# Stepper_driver_1_0.net
KiCad netlist of a schematic drawn in EAGLE
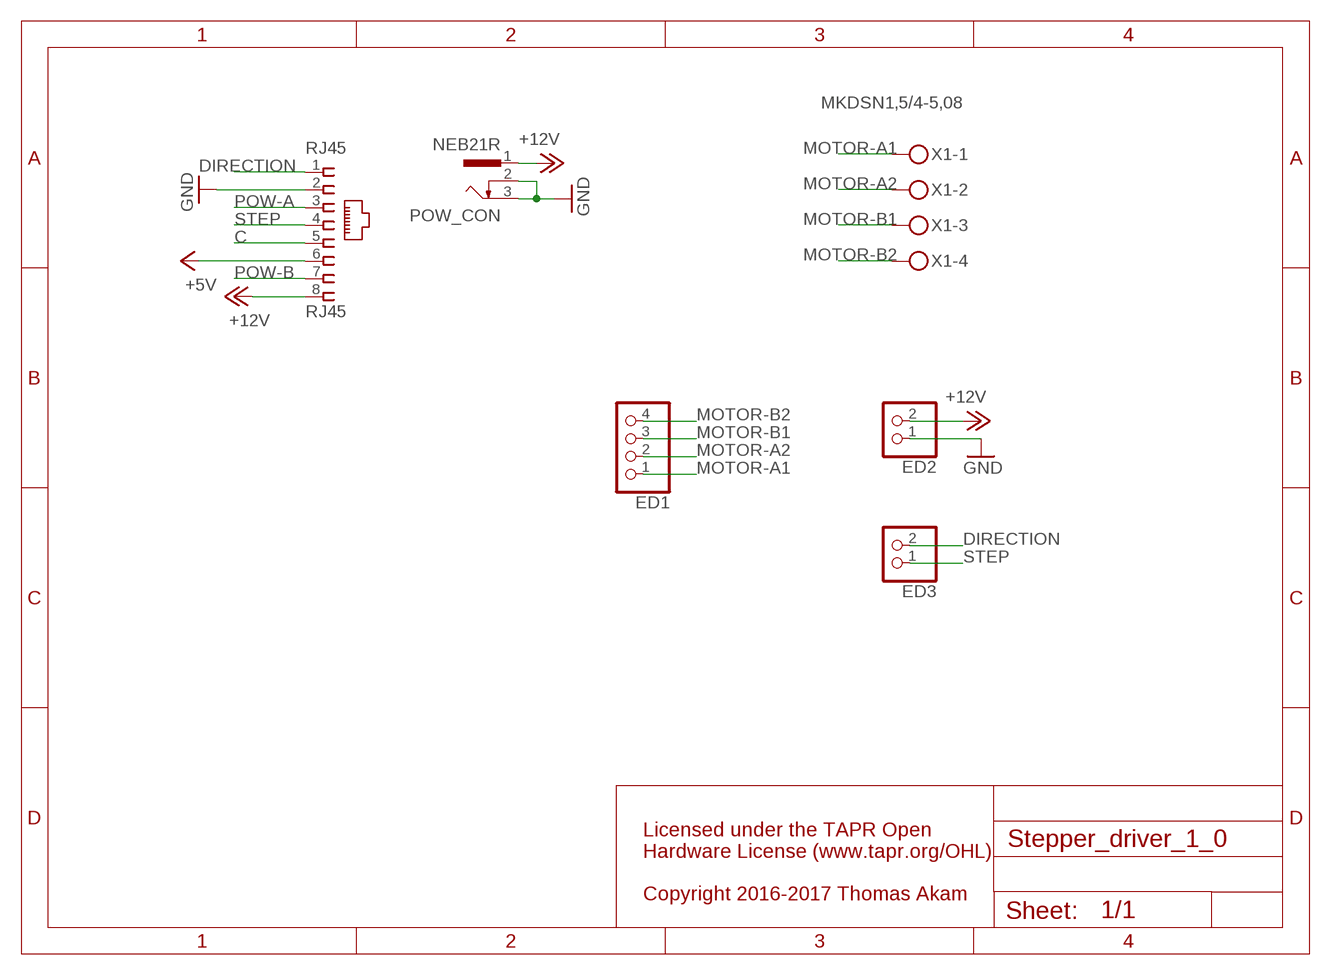
[diagram p0: schematic, sheet 1]

(export (version "E")
  (design (tool "Eeschema 10.0.6"))
  (components
    (comp (ref "ED1")
      (value "PINHD-1X4")
      (footprint "eagle-import:1X04")
      (libsource (lib "eagle-import") (part "PINHD-1X4"))
    )
    (comp (ref "ED2")
      (value "PINHD-1X2")
      (footprint "eagle-import:1X02")
      (libsource (lib "eagle-import") (part "PINHD-1X2"))
    )
    (comp (ref "ED3")
      (value "PINHD-1X2")
      (footprint "eagle-import:1X02")
      (libsource (lib "eagle-import") (part "PINHD-1X2"))
    )
    (comp (ref "POW_CON")
      (value "NEB21R")
      (footprint "eagle-import:NEB21R")
      (fields (field (name "MPN") "NEB 21 R"))
      (libsource (lib "eagle-import") (part "NEB21R"))
    )
    (comp (ref "RJ45")
      (value "RJ45")
      (footprint "eagle-import:RJ45-NO-SHIELD-VERTICAL")
      (libsource (lib "eagle-import") (part "RJ45VERTICAL"))
    )
    (comp (ref "X1")
      (value "MKDSN1,5/4-5,08")
      (footprint "eagle-import:MKDSN1,5_4-5,08")
      (libsource (lib "eagle-import") (part "MKDSN1,5/4-5,08"))
    )
  )
  (nets
    (net (code "1") (name "+5V") (class "Default")
      (node (ref "RJ45") (pin "6") (pinfunction "6_6") (pintype "passive"))
    )
    (net (code "2") (name "+12V") (class "Default")
      (node (ref "ED2") (pin "2") (pinfunction "2_2") (pintype "passive"))
      (node (ref "POW_CON") (pin "1") (pinfunction "1_1") (pintype "passive"))
      (node (ref "RJ45") (pin "8") (pinfunction "8_8") (pintype "passive"))
    )
    (net (code "3") (name "/C") (class "Default")
      (node (ref "RJ45") (pin "5") (pinfunction "5_5") (pintype "passive"))
    )
    (net (code "4") (name "/DIRECTION") (class "Default")
      (node (ref "ED3") (pin "2") (pinfunction "2_2") (pintype "passive"))
      (node (ref "RJ45") (pin "1") (pinfunction "1_1") (pintype "passive"))
    )
    (net (code "5") (name "/MOTOR-A1") (class "Default")
      (node (ref "ED1") (pin "1") (pinfunction "1_1") (pintype "passive"))
      (node (ref "X1") (pin "1") (pinfunction "KL_1") (pintype "passive"))
    )
    (net (code "6") (name "/MOTOR-A2") (class "Default")
      (node (ref "ED1") (pin "2") (pinfunction "2_2") (pintype "passive"))
      (node (ref "X1") (pin "2") (pinfunction "KL_2") (pintype "passive"))
    )
    (net (code "7") (name "/MOTOR-B1") (class "Default")
      (node (ref "ED1") (pin "3") (pinfunction "3_3") (pintype "passive"))
      (node (ref "X1") (pin "3") (pinfunction "KL_3") (pintype "passive"))
    )
    (net (code "8") (name "/MOTOR-B2") (class "Default")
      (node (ref "ED1") (pin "4") (pinfunction "4_4") (pintype "passive"))
      (node (ref "X1") (pin "4") (pinfunction "KL_4") (pintype "passive"))
    )
    (net (code "9") (name "/POW-A") (class "Default")
      (node (ref "RJ45") (pin "3") (pinfunction "3_3") (pintype "passive"))
    )
    (net (code "10") (name "/POW-B") (class "Default")
      (node (ref "RJ45") (pin "7") (pinfunction "7_7") (pintype "passive"))
    )
    (net (code "11") (name "/STEP") (class "Default")
      (node (ref "ED3") (pin "1") (pinfunction "1_1") (pintype "passive"))
      (node (ref "RJ45") (pin "4") (pinfunction "4_4") (pintype "passive"))
    )
    (net (code "12") (name "GND") (class "Default")
      (node (ref "ED2") (pin "1") (pinfunction "1_1") (pintype "passive"))
      (node (ref "POW_CON") (pin "2") (pinfunction "2_2") (pintype "passive"))
      (node (ref "POW_CON") (pin "3") (pinfunction "3_3") (pintype "passive"))
      (node (ref "RJ45") (pin "2") (pinfunction "2_2") (pintype "passive"))
    )
  )
)
